# POWER_EXTENSION.net
KiCad netlist of a schematic drawn in Altium Designer
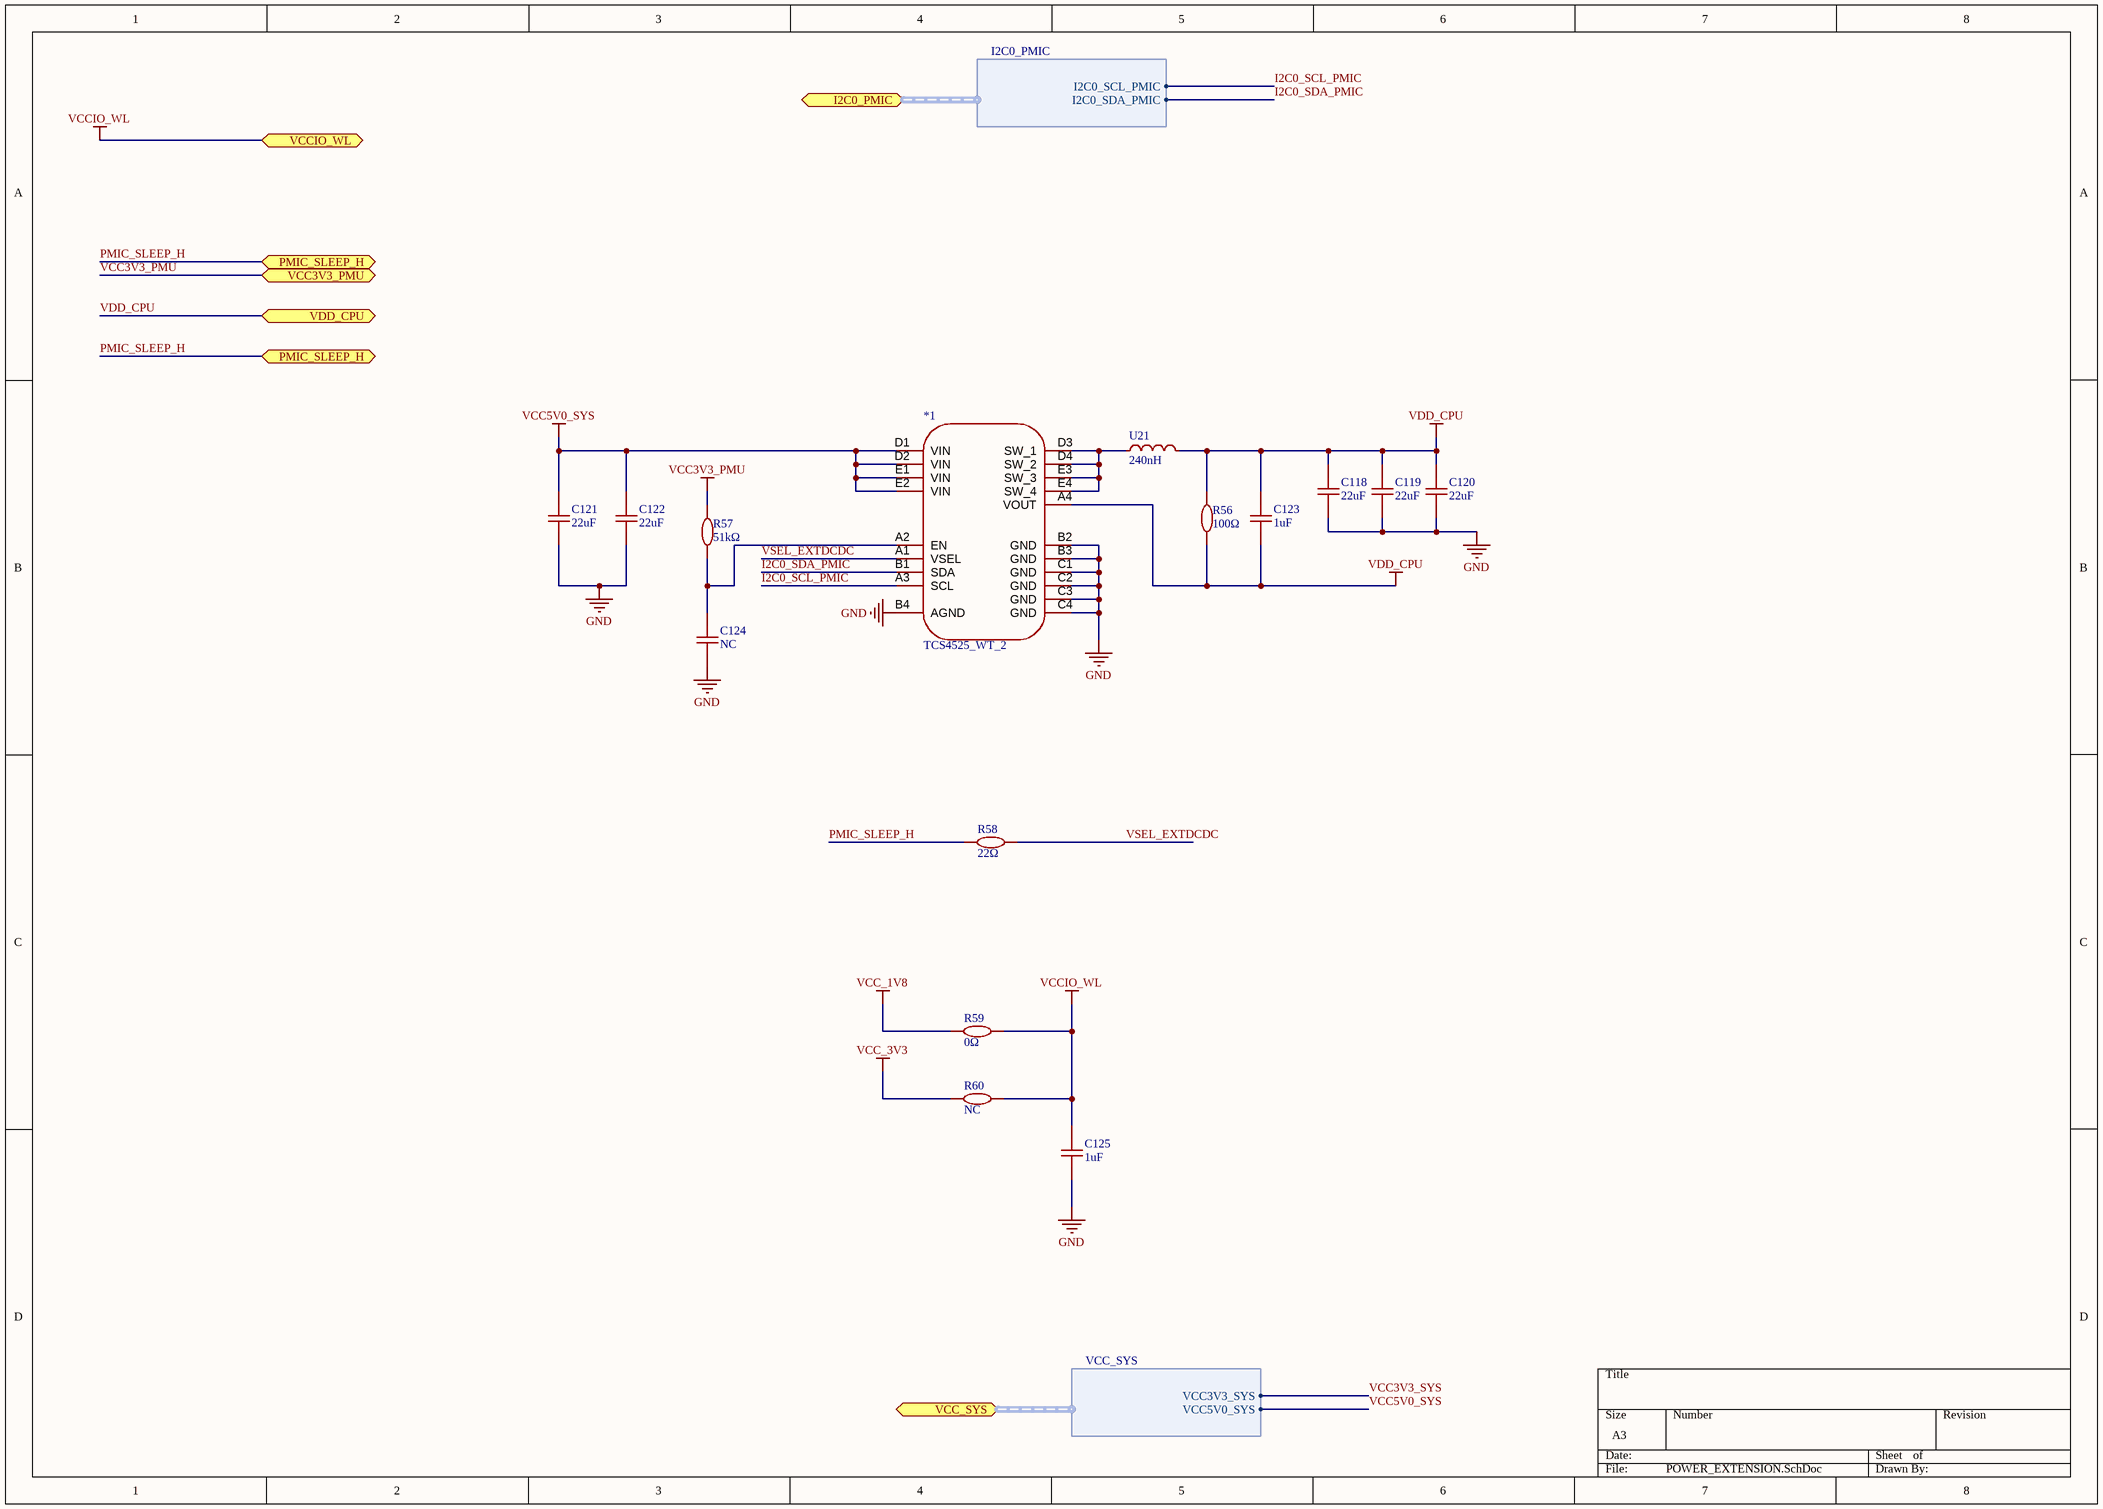
[diagram p0: POWER_EXTENSION.SchDoc]

(export (version "E")
  (design (tool "Eeschema 10.0.6"))
  (components
    (comp (ref "*1")
      (value "TCS4525_WT_2")
      (footprint "TCS4525")
      (description "LDO from TaoBao")
      (libsource (lib "LDO") (part "TCS4525_WT_2"))
    )
    (comp (ref "C118")
      (value "22uF")
      (footprint "C0603")
      (description "16V 22uF X5R ±20% 0603 Ceramic Capacitors ROHS")
      (libsource (lib "RLC") (part "22uF"))
    )
    (comp (ref "C119")
      (value "22uF")
      (footprint "C0603")
      (description "16V 22uF X5R ±20% 0603 Ceramic Capacitors ROHS")
      (libsource (lib "RLC") (part "22uF"))
    )
    (comp (ref "C120")
      (value "22uF")
      (footprint "C0603")
      (description "16V 22uF X5R ±20% 0603 Ceramic Capacitors ROHS")
      (libsource (lib "RLC") (part "22uF"))
    )
    (comp (ref "C121")
      (value "22uF")
      (footprint "C0603")
      (description "16V 22uF X5R ±20% 0603 Ceramic Capacitors ROHS")
      (libsource (lib "RLC") (part "22uF"))
    )
    (comp (ref "C122")
      (value "22uF")
      (footprint "C0603")
      (description "16V 22uF X5R ±20% 0603 Ceramic Capacitors ROHS")
      (libsource (lib "RLC") (part "22uF"))
    )
    (comp (ref "C123")
      (value "1uF")
      (footprint "C0402")
      (description "50V 1uF X5R ±10% 0402 Ceramic Capacitors ROHS")
      (libsource (lib "RLC") (part "1uF"))
    )
    (comp (ref "C124")
      (value "NC")
      (footprint "C0402")
      (description "50V 1nF X7R ±10% 0402 Ceramic Capacitors ROHS")
      (libsource (lib "RLC") (part "1nF"))
    )
    (comp (ref "C125")
      (value "1uF")
      (footprint "C0402")
      (description "50V 1uF X5R ±10% 0402 Ceramic Capacitors ROHS")
      (libsource (lib "RLC") (part "1uF"))
    )
    (comp (ref "R56")
      (value "100Ω")
      (footprint "R0402")
      (description "100Ω 62.5mW 50V ±100ppm/℃ Thick Film Resistor ±1% 0402 Chip Resistor - Surface Mount ROHS")
      (libsource (lib "RLC") (part "100Ω"))
    )
    (comp (ref "R57")
      (value "51kΩ")
      (footprint "R0402")
      (description "51kΩ 62.5mW 50V ±100ppm/℃ Thick Film Resistor ±1% 0402 Chip Resistor - Surface Mount ROHS")
      (libsource (lib "RLC") (part "51kΩ"))
    )
    (comp (ref "R58")
      (value "22Ω")
      (footprint "R0402")
      (description "小尺寸、重量轻。降低组装成本,与贴片机匹配。适用于波峰焊和回流焊")
      (libsource (lib "RLC") (part "22Ω"))
    )
    (comp (ref "R59")
      (value "0Ω")
      (footprint "R0402")
      (description "0Ω 62.5mW 50V Thick Film Resistor ±1% 0402 Chip Resistor - Surface Mount ROHS")
      (libsource (lib "RLC") (part "0Ω"))
    )
    (comp (ref "R60")
      (value "NC")
      (footprint "R0402")
      (description "0Ω 62.5mW 50V Thick Film Resistor ±1% 0402 Chip Resistor - Surface Mount ROHS")
      (libsource (lib "RLC") (part "0Ω"))
    )
    (comp (ref "U21")
      (value "240nH")
      (footprint "IND-SMD_L2.5-W2.0_WPN252012H")
      (libsource (lib "RLC") (part "WPN252012HR24MT"))
    )
  )
  (nets
    (net (code "3") (name "/I2C0_SCL_PMIC") (class "Default")
      (node (ref "*1") (pin "A3") (pinfunction "SCL_A3") (pintype "passive"))
    )
    (net (code "4") (name "/I2C0_SDA_PMIC") (class "Default")
      (node (ref "*1") (pin "B1") (pinfunction "SDA_B1") (pintype "passive"))
    )
    (net (code "5") (name "/PMIC_SLEEP_H") (class "Default")
      (node (ref "R58") (pin "1") (pinfunction "1_1") (pintype "passive"))
    )
    (net (code "7") (name "/VSEL_EXTDCDC") (class "Default")
      (node (ref "*1") (pin "A1") (pinfunction "VSEL_A1") (pintype "passive"))
      (node (ref "R58") (pin "2") (pinfunction "2_2") (pintype "passive"))
    )
    (net (code "10") (name "GND") (class "Default")
      (node (ref "*1") (pin "B2") (pinfunction "GND_B2") (pintype "passive"))
      (node (ref "*1") (pin "B3") (pinfunction "GND_B3") (pintype "passive"))
      (node (ref "*1") (pin "B4") (pinfunction "AGND_B4") (pintype "passive"))
      (node (ref "*1") (pin "C1") (pinfunction "GND_C1") (pintype "passive"))
      (node (ref "*1") (pin "C2") (pinfunction "GND_C2") (pintype "passive"))
      (node (ref "*1") (pin "C3") (pinfunction "GND_C3") (pintype "passive"))
      (node (ref "*1") (pin "C4") (pinfunction "GND_C4") (pintype "passive"))
      (node (ref "C118") (pin "1") (pinfunction "1_1") (pintype "passive"))
      (node (ref "C119") (pin "1") (pinfunction "1_1") (pintype "passive"))
      (node (ref "C120") (pin "1") (pinfunction "1_1") (pintype "passive"))
      (node (ref "C121") (pin "1") (pinfunction "1_1") (pintype "passive"))
      (node (ref "C122") (pin "1") (pinfunction "1_1") (pintype "passive"))
      (node (ref "C124") (pin "1") (pinfunction "1_1") (pintype "passive"))
      (node (ref "C125") (pin "1") (pinfunction "1_1") (pintype "passive"))
    )
    (net (code "11") (name "Net-(*1-EN)") (class "Default")
      (node (ref "*1") (pin "A2") (pinfunction "EN_A2") (pintype "passive"))
      (node (ref "C124") (pin "2") (pinfunction "2_2") (pintype "passive"))
      (node (ref "R57") (pin "1") (pinfunction "1_1") (pintype "passive"))
    )
    (net (code "12") (name "Net-(*1-SW_1)") (class "Default")
      (node (ref "*1") (pin "D3") (pinfunction "SW_1_D3") (pintype "passive"))
      (node (ref "*1") (pin "D4") (pinfunction "SW_2_D4") (pintype "passive"))
      (node (ref "*1") (pin "E3") (pinfunction "SW_3_E3") (pintype "passive"))
      (node (ref "*1") (pin "E4") (pinfunction "SW_4_E4") (pintype "passive"))
      (node (ref "U21") (pin "1") (pinfunction "1_1") (pintype "passive"))
    )
    (net (code "13") (name "VCC3V3_PMU") (class "Default")
      (node (ref "R57") (pin "2") (pinfunction "2_2") (pintype "passive"))
    )
    (net (code "14") (name "VCC5V0_SYS") (class "Default")
      (node (ref "*1") (pin "D1") (pinfunction "VIN_D1") (pintype "passive"))
      (node (ref "*1") (pin "D2") (pinfunction "VIN_D2") (pintype "passive"))
      (node (ref "*1") (pin "E1") (pinfunction "VIN_E1") (pintype "passive"))
      (node (ref "*1") (pin "E2") (pinfunction "VIN_E2") (pintype "passive"))
      (node (ref "C121") (pin "2") (pinfunction "2_2") (pintype "passive"))
      (node (ref "C122") (pin "2") (pinfunction "2_2") (pintype "passive"))
    )
    (net (code "15") (name "VCCIO_WL") (class "Default")
      (node (ref "C125") (pin "2") (pinfunction "2_2") (pintype "passive"))
      (node (ref "R59") (pin "2") (pinfunction "2_2") (pintype "passive"))
      (node (ref "R60") (pin "2") (pinfunction "2_2") (pintype "passive"))
    )
    (net (code "16") (name "VCC_1V8") (class "Default")
      (node (ref "R59") (pin "1") (pinfunction "1_1") (pintype "passive"))
    )
    (net (code "17") (name "VCC_3V3") (class "Default")
      (node (ref "R60") (pin "1") (pinfunction "1_1") (pintype "passive"))
    )
    (net (code "18") (name "VDD_CPU") (class "Default")
      (node (ref "*1") (pin "A4") (pinfunction "VOUT_A4") (pintype "passive"))
      (node (ref "C118") (pin "2") (pinfunction "2_2") (pintype "passive"))
      (node (ref "C119") (pin "2") (pinfunction "2_2") (pintype "passive"))
      (node (ref "C120") (pin "2") (pinfunction "2_2") (pintype "passive"))
      (node (ref "C123") (pin "1") (pinfunction "1_1") (pintype "passive"))
      (node (ref "C123") (pin "2") (pinfunction "2_2") (pintype "passive"))
      (node (ref "R56") (pin "1") (pinfunction "1_1") (pintype "passive"))
      (node (ref "R56") (pin "2") (pinfunction "2_2") (pintype "passive"))
      (node (ref "U21") (pin "2") (pinfunction "2_2") (pintype "passive"))
    )
  )
)
